# Nano_PCB.net
KiCad netlist of a schematic drawn in EAGLE
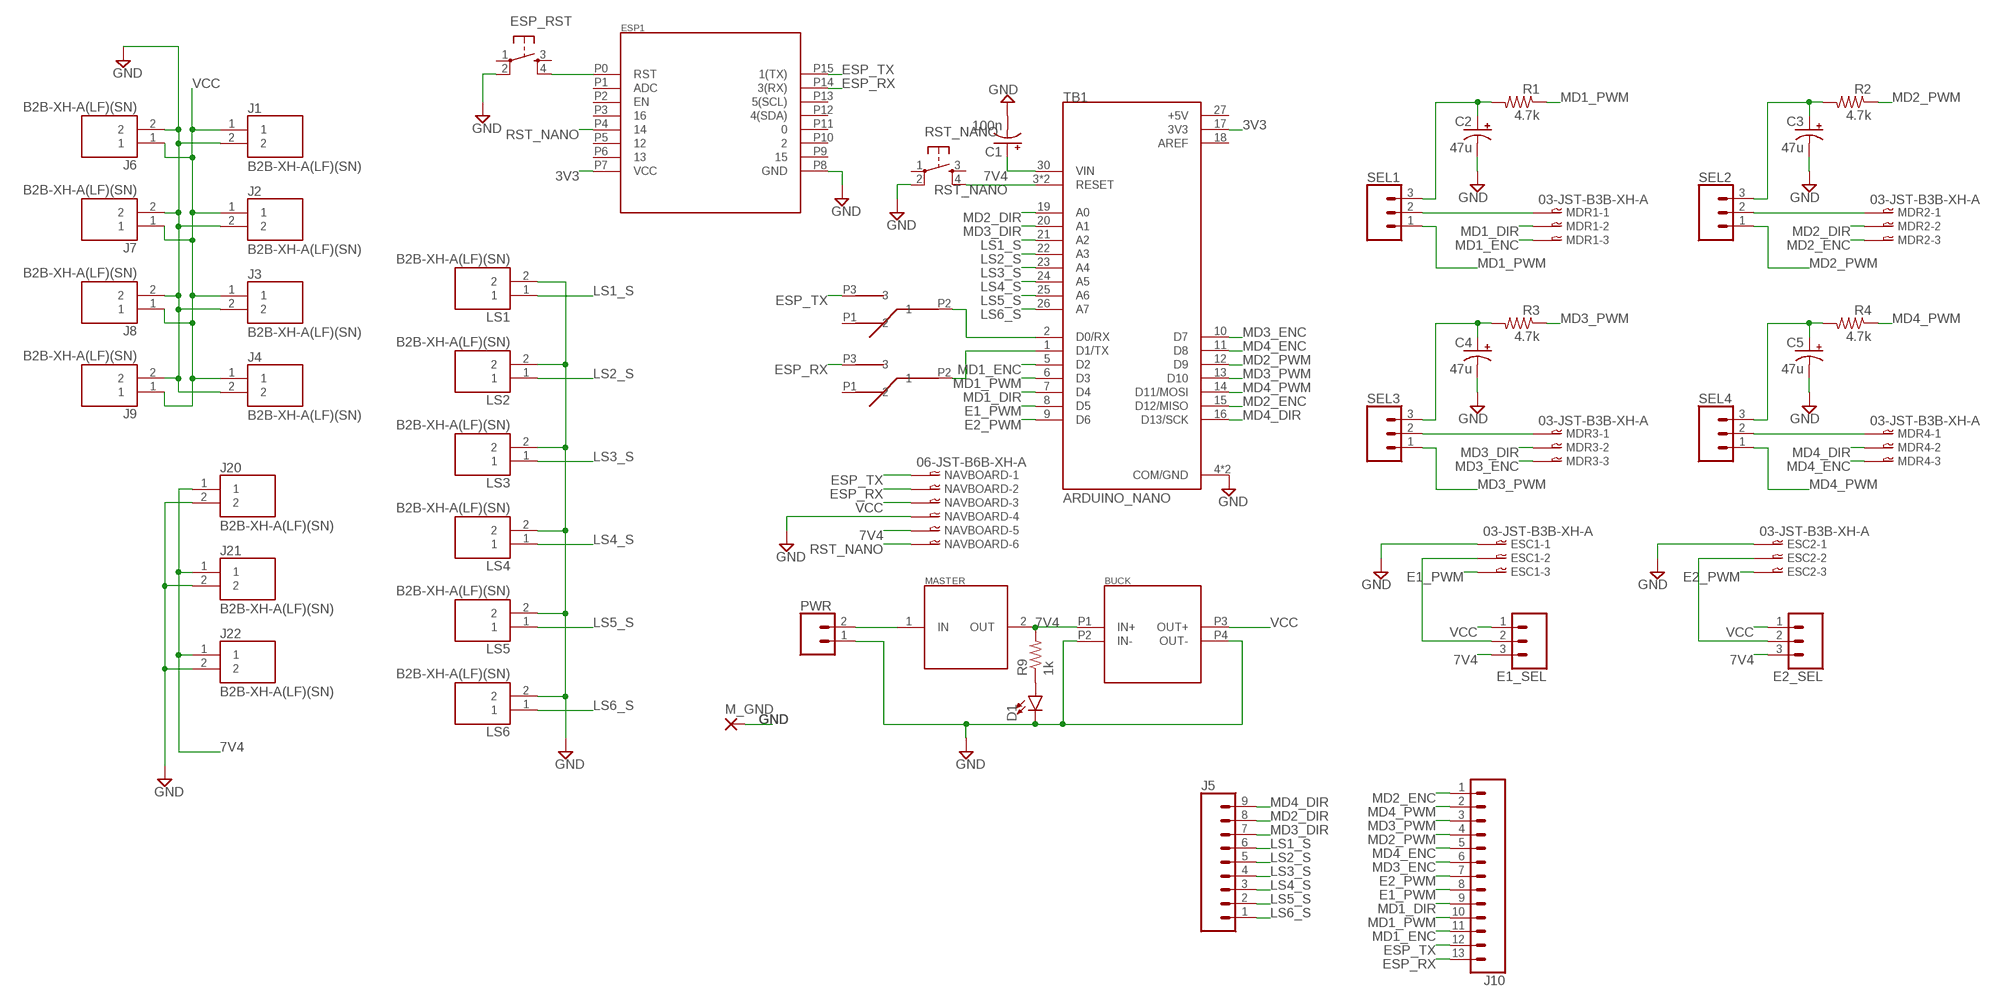
[diagram p0: schematic, sheet 1]

(export (version "E")
  (design (tool "Eeschema 10.0.6"))
  (components
    (comp (ref "BUCK")
      (value "5V_BUCK")
      (footprint "eagle-import:5V_BUCK")
      (libsource (lib "eagle-import") (part "5V_BUCK"))
    )
    (comp (ref "C1")
      (value "100n")
      (footprint "eagle-import:TT2D6")
      (libsource (lib "eagle-import") (part "CPOL-USTT2D6"))
    )
    (comp (ref "C2")
      (value "47u")
      (footprint "eagle-import:E2-5")
      (libsource (lib "eagle-import") (part "CPOL-USE2-5"))
    )
    (comp (ref "C3")
      (value "47u")
      (footprint "eagle-import:E2-5")
      (libsource (lib "eagle-import") (part "CPOL-USE2-5"))
    )
    (comp (ref "C4")
      (value "47u")
      (footprint "eagle-import:E2-5")
      (libsource (lib "eagle-import") (part "CPOL-USE2-5"))
    )
    (comp (ref "C5")
      (value "47u")
      (footprint "eagle-import:E2-5")
      (libsource (lib "eagle-import") (part "CPOL-USE2-5"))
    )
    (comp (ref "D1")
      (value "LED3MM")
      (footprint "eagle-import:LED_3MM")
      (libsource (lib "eagle-import") (part "LED3MM"))
    )
    (comp (ref "E1_SEL")
      (value "CONN_03")
      (footprint "eagle-import:1X03")
      (libsource (lib "eagle-import") (part "CONN_03"))
    )
    (comp (ref "E2_SEL")
      (value "CONN_03")
      (footprint "eagle-import:1X03")
      (libsource (lib "eagle-import") (part "CONN_03"))
    )
    (comp (ref "ESC1")
      (value "03-JST-B3B-XH-A")
      (footprint "eagle-import:B3B-XH")
      (libsource (lib "eagle-import") (part "03-JST-B3B-XH-A"))
    )
    (comp (ref "ESC2")
      (value "03-JST-B3B-XH-A")
      (footprint "eagle-import:B3B-XH")
      (libsource (lib "eagle-import") (part "03-JST-B3B-XH-A"))
    )
    (comp (ref "ESP1")
      (value "ESP07")
      (footprint "eagle-import:ESP07")
      (libsource (lib "eagle-import") (part "ESP07"))
    )
    (comp (ref "ESP_RST")
      (value "TAC_SWITCHPTH")
      (footprint "eagle-import:TACTILE-PTH")
      (libsource (lib "eagle-import") (part "TAC_SWITCHPTH"))
    )
    (comp (ref "J1")
      (value "B2B-XH-A(LF)(SN)")
      (footprint "eagle-import:JST_B2B-XH-A(LF)(SN)")
      (fields (field (name "MF") "JST Sales"))
      (libsource (lib "eagle-import") (part "B2B-XH-A(LF)(SN)"))
    )
    (comp (ref "J2")
      (value "B2B-XH-A(LF)(SN)")
      (footprint "eagle-import:JST_B2B-XH-A(LF)(SN)")
      (fields (field (name "MF") "JST Sales"))
      (libsource (lib "eagle-import") (part "B2B-XH-A(LF)(SN)"))
    )
    (comp (ref "J3")
      (value "B2B-XH-A(LF)(SN)")
      (footprint "eagle-import:JST_B2B-XH-A(LF)(SN)")
      (fields (field (name "MF") "JST Sales"))
      (libsource (lib "eagle-import") (part "B2B-XH-A(LF)(SN)"))
    )
    (comp (ref "J4")
      (value "B2B-XH-A(LF)(SN)")
      (footprint "eagle-import:JST_B2B-XH-A(LF)(SN)")
      (fields (field (name "MF") "JST Sales"))
      (libsource (lib "eagle-import") (part "B2B-XH-A(LF)(SN)"))
    )
    (comp (ref "J5")
      (value "CONN_09")
      (footprint "eagle-import:1X09")
      (libsource (lib "eagle-import") (part "CONN_09"))
    )
    (comp (ref "J6")
      (value "B2B-XH-A(LF)(SN)")
      (footprint "eagle-import:JST_B2B-XH-A(LF)(SN)")
      (fields (field (name "MF") "JST Sales"))
      (libsource (lib "eagle-import") (part "B2B-XH-A(LF)(SN)"))
    )
    (comp (ref "J7")
      (value "B2B-XH-A(LF)(SN)")
      (footprint "eagle-import:JST_B2B-XH-A(LF)(SN)")
      (fields (field (name "MF") "JST Sales"))
      (libsource (lib "eagle-import") (part "B2B-XH-A(LF)(SN)"))
    )
    (comp (ref "J8")
      (value "B2B-XH-A(LF)(SN)")
      (footprint "eagle-import:JST_B2B-XH-A(LF)(SN)")
      (fields (field (name "MF") "JST Sales"))
      (libsource (lib "eagle-import") (part "B2B-XH-A(LF)(SN)"))
    )
    (comp (ref "J9")
      (value "B2B-XH-A(LF)(SN)")
      (footprint "eagle-import:JST_B2B-XH-A(LF)(SN)")
      (fields (field (name "MF") "JST Sales"))
      (libsource (lib "eagle-import") (part "B2B-XH-A(LF)(SN)"))
    )
    (comp (ref "J10")
      (value "CONN_13")
      (footprint "eagle-import:1X13")
      (libsource (lib "eagle-import") (part "CONN_13"))
    )
    (comp (ref "J20")
      (value "B2B-XH-A(LF)(SN)")
      (footprint "eagle-import:JST_B2B-XH-A(LF)(SN)")
      (fields (field (name "MF") "JST Sales"))
      (libsource (lib "eagle-import") (part "B2B-XH-A(LF)(SN)"))
    )
    (comp (ref "J21")
      (value "B2B-XH-A(LF)(SN)")
      (footprint "eagle-import:JST_B2B-XH-A(LF)(SN)")
      (fields (field (name "MF") "JST Sales"))
      (libsource (lib "eagle-import") (part "B2B-XH-A(LF)(SN)"))
    )
    (comp (ref "J22")
      (value "B2B-XH-A(LF)(SN)")
      (footprint "eagle-import:JST_B2B-XH-A(LF)(SN)")
      (fields (field (name "MF") "JST Sales"))
      (libsource (lib "eagle-import") (part "B2B-XH-A(LF)(SN)"))
    )
    (comp (ref "LS1")
      (value "B2B-XH-A(LF)(SN)")
      (footprint "eagle-import:JST_B2B-XH-A(LF)(SN)")
      (fields (field (name "MF") "JST Sales"))
      (libsource (lib "eagle-import") (part "B2B-XH-A(LF)(SN)"))
    )
    (comp (ref "LS2")
      (value "B2B-XH-A(LF)(SN)")
      (footprint "eagle-import:JST_B2B-XH-A(LF)(SN)")
      (fields (field (name "MF") "JST Sales"))
      (libsource (lib "eagle-import") (part "B2B-XH-A(LF)(SN)"))
    )
    (comp (ref "LS3")
      (value "B2B-XH-A(LF)(SN)")
      (footprint "eagle-import:JST_B2B-XH-A(LF)(SN)")
      (fields (field (name "MF") "JST Sales"))
      (libsource (lib "eagle-import") (part "B2B-XH-A(LF)(SN)"))
    )
    (comp (ref "LS4")
      (value "B2B-XH-A(LF)(SN)")
      (footprint "eagle-import:JST_B2B-XH-A(LF)(SN)")
      (fields (field (name "MF") "JST Sales"))
      (libsource (lib "eagle-import") (part "B2B-XH-A(LF)(SN)"))
    )
    (comp (ref "LS5")
      (value "B2B-XH-A(LF)(SN)")
      (footprint "eagle-import:JST_B2B-XH-A(LF)(SN)")
      (fields (field (name "MF") "JST Sales"))
      (libsource (lib "eagle-import") (part "B2B-XH-A(LF)(SN)"))
    )
    (comp (ref "LS6")
      (value "B2B-XH-A(LF)(SN)")
      (footprint "eagle-import:JST_B2B-XH-A(LF)(SN)")
      (fields (field (name "MF") "JST Sales"))
      (libsource (lib "eagle-import") (part "B2B-XH-A(LF)(SN)"))
    )
    (comp (ref "MASTER")
      (value "MED_SWITCH")
      (footprint "eagle-import:MED_SWITCH")
      (libsource (lib "eagle-import") (part "MED_SWITCH"))
    )
    (comp (ref "MDR1")
      (value "03-JST-B3B-XH-A")
      (footprint "eagle-import:B3B-XH")
      (libsource (lib "eagle-import") (part "03-JST-B3B-XH-A"))
    )
    (comp (ref "MDR2")
      (value "03-JST-B3B-XH-A")
      (footprint "eagle-import:B3B-XH")
      (libsource (lib "eagle-import") (part "03-JST-B3B-XH-A"))
    )
    (comp (ref "MDR3")
      (value "03-JST-B3B-XH-A")
      (footprint "eagle-import:B3B-XH")
      (libsource (lib "eagle-import") (part "03-JST-B3B-XH-A"))
    )
    (comp (ref "MDR4")
      (value "03-JST-B3B-XH-A")
      (footprint "eagle-import:B3B-XH")
      (libsource (lib "eagle-import") (part "03-JST-B3B-XH-A"))
    )
    (comp (ref "M_GND")
      (value "WIREPADSMD5-2,5")
      (footprint "eagle-import:5-2,5")
      (libsource (lib "eagle-import") (part "WIREPADSMD5-2,5"))
    )
    (comp (ref "NAVBOARD")
      (value "06-JST-B6B-XH-A")
      (footprint "eagle-import:B6B-XH")
      (libsource (lib "eagle-import") (part "06-JST-B6B-XH-A"))
    )
    (comp (ref "PWR")
      (value "CONN_02PTH4")
      (footprint "eagle-import:1X02_XTRA_BIG")
      (libsource (lib "eagle-import") (part "CONN_02PTH4"))
    )
    (comp (ref "R1")
      (value "4.7k")
      (footprint "eagle-import:0204_7")
      (libsource (lib "eagle-import") (part "R-US_0204/7"))
    )
    (comp (ref "R2")
      (value "4.7k")
      (footprint "eagle-import:0204_7")
      (libsource (lib "eagle-import") (part "R-US_0204/7"))
    )
    (comp (ref "R3")
      (value "4.7k")
      (footprint "eagle-import:0204_7")
      (libsource (lib "eagle-import") (part "R-US_0204/7"))
    )
    (comp (ref "R4")
      (value "4.7k")
      (footprint "eagle-import:0204_7")
      (libsource (lib "eagle-import") (part "R-US_0204/7"))
    )
    (comp (ref "R9")
      (value "1k")
      (footprint "eagle-import:0204_7")
      (libsource (lib "eagle-import") (part "R-US_0204/7"))
    )
    (comp (ref "RST_NANO")
      (value "TAC_SWITCHPTH")
      (footprint "eagle-import:TACTILE-PTH")
      (libsource (lib "eagle-import") (part "TAC_SWITCHPTH"))
    )
    (comp (ref "SEL1")
      (value "CONN_03")
      (footprint "eagle-import:1X03")
      (libsource (lib "eagle-import") (part "CONN_03"))
    )
    (comp (ref "SEL2")
      (value "CONN_03")
      (footprint "eagle-import:1X03")
      (libsource (lib "eagle-import") (part "CONN_03"))
    )
    (comp (ref "SEL3")
      (value "CONN_03")
      (footprint "eagle-import:1X03")
      (libsource (lib "eagle-import") (part "CONN_03"))
    )
    (comp (ref "SEL4")
      (value "CONN_03")
      (footprint "eagle-import:1X03")
      (libsource (lib "eagle-import") (part "CONN_03"))
    )
    (comp (ref "TB1")
      (value "ARDUINO_NANO")
      (footprint "eagle-import:SHIELD_ARDUINO_NANO")
      (fields (field (name "MF") "Arduino") (field (name "MP") "Arduino Nano"))
      (libsource (lib "eagle-import") (part "ARDUINO_NANO"))
    )
    (comp (ref "U$1")
      (value "SLIDE_SWITCH")
      (footprint "eagle-import:SLIDE_SWITCH")
      (libsource (lib "eagle-import") (part "SLIDE_SWITCH"))
    )
    (comp (ref "U$2")
      (value "SLIDE_SWITCH")
      (footprint "eagle-import:SLIDE_SWITCH")
      (libsource (lib "eagle-import") (part "SLIDE_SWITCH"))
    )
  )
  (nets
    (net (code "1") (name "/+5V") (class "Default")
      (node (ref "TB1") (pin "27") (pinfunction "+5V_27") (pintype "power_in"))
    )
    (net (code "2") (name "/3V3") (class "Default")
      (node (ref "ESP1") (pin "P7") (pinfunction "VCC_P7") (pintype "bidirectional"))
      (node (ref "TB1") (pin "17") (pinfunction "3V3_17") (pintype "power_in"))
    )
    (net (code "3") (name "/7V4") (class "Default")
      (node (ref "BUCK") (pin "P1") (pinfunction "IN+_P1") (pintype "bidirectional"))
      (node (ref "C1") (pin "+") (pinfunction "+_+") (pintype "passive"))
      (node (ref "E1_SEL") (pin "3") (pinfunction "3_3") (pintype "passive"))
      (node (ref "E2_SEL") (pin "3") (pinfunction "3_3") (pintype "passive"))
      (node (ref "J20") (pin "1") (pinfunction "1_1") (pintype "passive"))
      (node (ref "J21") (pin "1") (pinfunction "1_1") (pintype "passive"))
      (node (ref "J22") (pin "1") (pinfunction "1_1") (pintype "passive"))
      (node (ref "MASTER") (pin "2") (pinfunction "OUT_2") (pintype "bidirectional"))
      (node (ref "NAVBOARD") (pin "P$5") (pinfunction "1_P$5") (pintype "passive"))
      (node (ref "R9") (pin "2") (pinfunction "2_2") (pintype "passive"))
      (node (ref "TB1") (pin "30") (pinfunction "VIN_30") (pintype "input"))
    )
    (net (code "4") (name "/AREF") (class "Default")
      (node (ref "TB1") (pin "18") (pinfunction "AREF_18") (pintype "power_in"))
    )
    (net (code "5") (name "/E1_PWM") (class "Default")
      (node (ref "ESC1") (pin "P$3") (pinfunction "1_P$3") (pintype "passive"))
      (node (ref "J10") (pin "8") (pinfunction "8_8") (pintype "passive"))
      (node (ref "TB1") (pin "8") (pinfunction "D5_8") (pintype "bidirectional"))
    )
    (net (code "6") (name "/E2_PWM") (class "Default")
      (node (ref "ESC2") (pin "P$3") (pinfunction "1_P$3") (pintype "passive"))
      (node (ref "J10") (pin "7") (pinfunction "7_7") (pintype "passive"))
      (node (ref "TB1") (pin "9") (pinfunction "D6_9") (pintype "bidirectional"))
    )
    (net (code "7") (name "/ESP_RX") (class "Default")
      (node (ref "ESP1") (pin "P14") (pinfunction "3(RX)_P14") (pintype "bidirectional"))
      (node (ref "J10") (pin "13") (pinfunction "13_13") (pintype "passive"))
      (node (ref "NAVBOARD") (pin "P$2") (pinfunction "1_P$2") (pintype "passive"))
      (node (ref "U$2") (pin "P3") (pinfunction "3_P3") (pintype "bidirectional"))
    )
    (net (code "8") (name "/ESP_TX") (class "Default")
      (node (ref "ESP1") (pin "P15") (pinfunction "1(TX)_P15") (pintype "bidirectional"))
      (node (ref "J10") (pin "12") (pinfunction "12_12") (pintype "passive"))
      (node (ref "NAVBOARD") (pin "P$1") (pinfunction "1_P$1") (pintype "passive"))
      (node (ref "U$1") (pin "P3") (pinfunction "3_P3") (pintype "bidirectional"))
    )
    (net (code "9") (name "/LS1_S") (class "Default")
      (node (ref "J5") (pin "6") (pinfunction "6_6") (pintype "passive"))
      (node (ref "LS1") (pin "1") (pinfunction "1_1") (pintype "passive"))
      (node (ref "TB1") (pin "21") (pinfunction "A2_21") (pintype "input"))
    )
    (net (code "10") (name "/LS2_S") (class "Default")
      (node (ref "J5") (pin "5") (pinfunction "5_5") (pintype "passive"))
      (node (ref "LS2") (pin "1") (pinfunction "1_1") (pintype "passive"))
      (node (ref "TB1") (pin "22") (pinfunction "A3_22") (pintype "input"))
    )
    (net (code "11") (name "/LS3_S") (class "Default")
      (node (ref "J5") (pin "4") (pinfunction "4_4") (pintype "passive"))
      (node (ref "LS3") (pin "1") (pinfunction "1_1") (pintype "passive"))
      (node (ref "TB1") (pin "23") (pinfunction "A4_23") (pintype "input"))
    )
    (net (code "12") (name "/LS4_S") (class "Default")
      (node (ref "J5") (pin "3") (pinfunction "3_3") (pintype "passive"))
      (node (ref "LS4") (pin "1") (pinfunction "1_1") (pintype "passive"))
      (node (ref "TB1") (pin "24") (pinfunction "A5_24") (pintype "input"))
    )
    (net (code "13") (name "/LS5_S") (class "Default")
      (node (ref "J5") (pin "2") (pinfunction "2_2") (pintype "passive"))
      (node (ref "LS5") (pin "1") (pinfunction "1_1") (pintype "passive"))
      (node (ref "TB1") (pin "25") (pinfunction "A6_25") (pintype "input"))
    )
    (net (code "14") (name "/LS6_S") (class "Default")
      (node (ref "J5") (pin "1") (pinfunction "1_1") (pintype "passive"))
      (node (ref "LS6") (pin "1") (pinfunction "1_1") (pintype "passive"))
      (node (ref "TB1") (pin "26") (pinfunction "A7_26") (pintype "input"))
    )
    (net (code "15") (name "/MD1_DIR") (class "Default")
      (node (ref "J10") (pin "9") (pinfunction "9_9") (pintype "passive"))
      (node (ref "MDR1") (pin "P$2") (pinfunction "1_P$2") (pintype "passive"))
      (node (ref "TB1") (pin "7") (pinfunction "D4_7") (pintype "bidirectional"))
    )
    (net (code "16") (name "/MD1_ENC") (class "Default")
      (node (ref "J10") (pin "11") (pinfunction "11_11") (pintype "passive"))
      (node (ref "MDR1") (pin "P$3") (pinfunction "1_P$3") (pintype "passive"))
      (node (ref "TB1") (pin "5") (pinfunction "D2_5") (pintype "bidirectional"))
    )
    (net (code "17") (name "/MD1_PWM") (class "Default")
      (node (ref "J10") (pin "10") (pinfunction "10_10") (pintype "passive"))
      (node (ref "R1") (pin "1") (pinfunction "1_1") (pintype "passive"))
      (node (ref "SEL1") (pin "1") (pinfunction "1_1") (pintype "passive"))
      (node (ref "TB1") (pin "6") (pinfunction "D3_6") (pintype "bidirectional"))
    )
    (net (code "18") (name "/MD2_DIR") (class "Default")
      (node (ref "J5") (pin "8") (pinfunction "8_8") (pintype "passive"))
      (node (ref "MDR2") (pin "P$2") (pinfunction "1_P$2") (pintype "passive"))
      (node (ref "TB1") (pin "19") (pinfunction "A0_19") (pintype "input"))
    )
    (net (code "19") (name "/MD2_ENC") (class "Default")
      (node (ref "J10") (pin "1") (pinfunction "1_1") (pintype "passive"))
      (node (ref "MDR2") (pin "P$3") (pinfunction "1_P$3") (pintype "passive"))
      (node (ref "TB1") (pin "15") (pinfunction "D12/MISO_15") (pintype "bidirectional"))
    )
    (net (code "20") (name "/MD2_PWM") (class "Default")
      (node (ref "J10") (pin "4") (pinfunction "4_4") (pintype "passive"))
      (node (ref "R2") (pin "1") (pinfunction "1_1") (pintype "passive"))
      (node (ref "SEL2") (pin "1") (pinfunction "1_1") (pintype "passive"))
      (node (ref "TB1") (pin "12") (pinfunction "D9_12") (pintype "bidirectional"))
    )
    (net (code "21") (name "/MD3_DIR") (class "Default")
      (node (ref "J5") (pin "7") (pinfunction "7_7") (pintype "passive"))
      (node (ref "MDR3") (pin "P$2") (pinfunction "1_P$2") (pintype "passive"))
      (node (ref "TB1") (pin "20") (pinfunction "A1_20") (pintype "input"))
    )
    (net (code "22") (name "/MD3_ENC") (class "Default")
      (node (ref "J10") (pin "6") (pinfunction "6_6") (pintype "passive"))
      (node (ref "MDR3") (pin "P$3") (pinfunction "1_P$3") (pintype "passive"))
      (node (ref "TB1") (pin "10") (pinfunction "D7_10") (pintype "bidirectional"))
    )
    (net (code "23") (name "/MD3_PWM") (class "Default")
      (node (ref "J10") (pin "3") (pinfunction "3_3") (pintype "passive"))
      (node (ref "R3") (pin "1") (pinfunction "1_1") (pintype "passive"))
      (node (ref "SEL3") (pin "1") (pinfunction "1_1") (pintype "passive"))
      (node (ref "TB1") (pin "13") (pinfunction "D10_13") (pintype "bidirectional"))
    )
    (net (code "24") (name "/MD4_DIR") (class "Default")
      (node (ref "J5") (pin "9") (pinfunction "9_9") (pintype "passive"))
      (node (ref "MDR4") (pin "P$2") (pinfunction "1_P$2") (pintype "passive"))
      (node (ref "TB1") (pin "16") (pinfunction "D13/SCK_16") (pintype "bidirectional"))
    )
    (net (code "25") (name "/MD4_ENC") (class "Default")
      (node (ref "J10") (pin "5") (pinfunction "5_5") (pintype "passive"))
      (node (ref "MDR4") (pin "P$3") (pinfunction "1_P$3") (pintype "passive"))
      (node (ref "TB1") (pin "11") (pinfunction "D8_11") (pintype "bidirectional"))
    )
    (net (code "26") (name "/MD4_PWM") (class "Default")
      (node (ref "J10") (pin "2") (pinfunction "2_2") (pintype "passive"))
      (node (ref "R4") (pin "1") (pinfunction "1_1") (pintype "passive"))
      (node (ref "SEL4") (pin "1") (pinfunction "1_1") (pintype "passive"))
      (node (ref "TB1") (pin "14") (pinfunction "D11/MOSI_14") (pintype "bidirectional"))
    )
    (net (code "27") (name "/RST_NANO") (class "Default")
      (node (ref "ESP1") (pin "P4") (pinfunction "14_P4") (pintype "bidirectional"))
      (node (ref "NAVBOARD") (pin "P$6") (pinfunction "1_P$6") (pintype "passive"))
      (node (ref "RST_NANO") (pin "4") (pinfunction "4_4") (pintype "passive"))
      (node (ref "TB1") (pin "28") (pinfunction "RESET_28") (pintype "input"))
      (node (ref "TB1") (pin "3") (pinfunction "RESET_3") (pintype "input"))
    )
    (net (code "28") (name "/VCC") (class "Default")
      (node (ref "BUCK") (pin "P3") (pinfunction "OUT+_P3") (pintype "bidirectional"))
      (node (ref "E1_SEL") (pin "1") (pinfunction "1_1") (pintype "passive"))
      (node (ref "E2_SEL") (pin "1") (pinfunction "1_1") (pintype "passive"))
      (node (ref "J1") (pin "1") (pinfunction "1_1") (pintype "passive"))
      (node (ref "J2") (pin "1") (pinfunction "1_1") (pintype "passive"))
      (node (ref "J3") (pin "1") (pinfunction "1_1") (pintype "passive"))
      (node (ref "J4") (pin "1") (pinfunction "1_1") (pintype "passive"))
      (node (ref "J6") (pin "1") (pinfunction "1_1") (pintype "passive"))
      (node (ref "J7") (pin "1") (pinfunction "1_1") (pintype "passive"))
      (node (ref "J8") (pin "1") (pinfunction "1_1") (pintype "passive"))
      (node (ref "J9") (pin "1") (pinfunction "1_1") (pintype "passive"))
      (node (ref "NAVBOARD") (pin "P$3") (pinfunction "1_P$3") (pintype "passive"))
    )
    (net (code "29") (name "GND") (class "Default")
      (node (ref "BUCK") (pin "P2") (pinfunction "IN-_P2") (pintype "bidirectional"))
      (node (ref "BUCK") (pin "P4") (pinfunction "OUT-_P4") (pintype "bidirectional"))
      (node (ref "C1") (pin "-") (pinfunction "-_-") (pintype "passive"))
      (node (ref "C2") (pin "-") (pinfunction "-_-") (pintype "passive"))
      (node (ref "C3") (pin "-") (pinfunction "-_-") (pintype "passive"))
      (node (ref "C4") (pin "-") (pinfunction "-_-") (pintype "passive"))
      (node (ref "C5") (pin "-") (pinfunction "-_-") (pintype "passive"))
      (node (ref "D1") (pin "K") (pinfunction "C_K") (pintype "passive"))
      (node (ref "ESC1") (pin "P$1") (pinfunction "1_P$1") (pintype "passive"))
      (node (ref "ESC2") (pin "P$1") (pinfunction "1_P$1") (pintype "passive"))
      (node (ref "ESP1") (pin "P8") (pinfunction "GND_P8") (pintype "bidirectional"))
      (node (ref "ESP_RST") (pin "2") (pinfunction "2_2") (pintype "passive"))
      (node (ref "J1") (pin "2") (pinfunction "2_2") (pintype "passive"))
      (node (ref "J2") (pin "2") (pinfunction "2_2") (pintype "passive"))
      (node (ref "J20") (pin "2") (pinfunction "2_2") (pintype "passive"))
      (node (ref "J21") (pin "2") (pinfunction "2_2") (pintype "passive"))
      (node (ref "J22") (pin "2") (pinfunction "2_2") (pintype "passive"))
      (node (ref "J3") (pin "2") (pinfunction "2_2") (pintype "passive"))
      (node (ref "J4") (pin "2") (pinfunction "2_2") (pintype "passive"))
      (node (ref "J6") (pin "2") (pinfunction "2_2") (pintype "passive"))
      (node (ref "J7") (pin "2") (pinfunction "2_2") (pintype "passive"))
      (node (ref "J8") (pin "2") (pinfunction "2_2") (pintype "passive"))
      (node (ref "J9") (pin "2") (pinfunction "2_2") (pintype "passive"))
      (node (ref "LS1") (pin "2") (pinfunction "2_2") (pintype "passive"))
      (node (ref "LS2") (pin "2") (pinfunction "2_2") (pintype "passive"))
      (node (ref "LS3") (pin "2") (pinfunction "2_2") (pintype "passive"))
      (node (ref "LS4") (pin "2") (pinfunction "2_2") (pintype "passive"))
      (node (ref "LS5") (pin "2") (pinfunction "2_2") (pintype "passive"))
      (node (ref "LS6") (pin "2") (pinfunction "2_2") (pintype "passive"))
      (node (ref "M_GND") (pin "1") (pinfunction "P_1") (pintype "passive"))
      (node (ref "NAVBOARD") (pin "P$4") (pinfunction "1_P$4") (pintype "passive"))
      (node (ref "PWR") (pin "1") (pinfunction "1_1") (pintype "passive"))
      (node (ref "RST_NANO") (pin "2") (pinfunction "2_2") (pintype "passive"))
      (node (ref "TB1") (pin "29") (pinfunction "COM/GND_29") (pintype "power_in"))
      (node (ref "TB1") (pin "4") (pinfunction "COM/GND_4") (pintype "power_in"))
    )
    (net (code "30") (name "Net-(C2-Pad+)") (class "Default")
      (node (ref "C2") (pin "+") (pinfunction "+_+") (pintype "passive"))
      (node (ref "R1") (pin "2") (pinfunction "2_2") (pintype "passive"))
      (node (ref "SEL1") (pin "3") (pinfunction "3_3") (pintype "passive"))
    )
    (net (code "31") (name "Net-(C3-Pad+)") (class "Default")
      (node (ref "C3") (pin "+") (pinfunction "+_+") (pintype "passive"))
      (node (ref "R2") (pin "2") (pinfunction "2_2") (pintype "passive"))
      (node (ref "SEL2") (pin "3") (pinfunction "3_3") (pintype "passive"))
    )
    (net (code "32") (name "Net-(C4-Pad+)") (class "Default")
      (node (ref "C4") (pin "+") (pinfunction "+_+") (pintype "passive"))
      (node (ref "R3") (pin "2") (pinfunction "2_2") (pintype "passive"))
      (node (ref "SEL3") (pin "3") (pinfunction "3_3") (pintype "passive"))
    )
    (net (code "33") (name "Net-(C5-Pad+)") (class "Default")
      (node (ref "C5") (pin "+") (pinfunction "+_+") (pintype "passive"))
      (node (ref "R4") (pin "2") (pinfunction "2_2") (pintype "passive"))
      (node (ref "SEL4") (pin "3") (pinfunction "3_3") (pintype "passive"))
    )
    (net (code "34") (name "Net-(D1-PadA)") (class "Default")
      (node (ref "D1") (pin "A") (pinfunction "A_A") (pintype "passive"))
      (node (ref "R9") (pin "1") (pinfunction "1_1") (pintype "passive"))
    )
    (net (code "35") (name "Net-(ESC1B-1)") (class "Default")
      (node (ref "E1_SEL") (pin "2") (pinfunction "2_2") (pintype "passive"))
      (node (ref "ESC1") (pin "P$2") (pinfunction "1_P$2") (pintype "passive"))
    )
    (net (code "36") (name "Net-(ESC2B-1)") (class "Default")
      (node (ref "E2_SEL") (pin "2") (pinfunction "2_2") (pintype "passive"))
      (node (ref "ESC2") (pin "P$2") (pinfunction "1_P$2") (pintype "passive"))
    )
    (net (code "37") (name "Net-(ESP1-RST)") (class "Default")
      (node (ref "ESP1") (pin "P0") (pinfunction "RST_P0") (pintype "bidirectional"))
      (node (ref "ESP_RST") (pin "4") (pinfunction "4_4") (pintype "passive"))
    )
    (net (code "38") (name "Net-(MASTER-IN)") (class "Default")
      (node (ref "MASTER") (pin "1") (pinfunction "IN_1") (pintype "bidirectional"))
      (node (ref "PWR") (pin "2") (pinfunction "2_2") (pintype "passive"))
    )
    (net (code "39") (name "Net-(MDR1A-1)") (class "Default")
      (node (ref "MDR1") (pin "P$1") (pinfunction "1_P$1") (pintype "passive"))
      (node (ref "SEL1") (pin "2") (pinfunction "2_2") (pintype "passive"))
    )
    (net (code "40") (name "Net-(MDR2A-1)") (class "Default")
      (node (ref "MDR2") (pin "P$1") (pinfunction "1_P$1") (pintype "passive"))
      (node (ref "SEL2") (pin "2") (pinfunction "2_2") (pintype "passive"))
    )
    (net (code "41") (name "Net-(MDR3A-1)") (class "Default")
      (node (ref "MDR3") (pin "P$1") (pinfunction "1_P$1") (pintype "passive"))
      (node (ref "SEL3") (pin "2") (pinfunction "2_2") (pintype "passive"))
    )
    (net (code "42") (name "Net-(MDR4A-1)") (class "Default")
      (node (ref "MDR4") (pin "P$1") (pinfunction "1_P$1") (pintype "passive"))
      (node (ref "SEL4") (pin "2") (pinfunction "2_2") (pintype "passive"))
    )
    (net (code "43") (name "Net-(TB1-D0{slash}RX)") (class "Default")
      (node (ref "TB1") (pin "2") (pinfunction "D0/RX_2") (pintype "bidirectional"))
      (node (ref "U$1") (pin "P2") (pinfunction "1_P2") (pintype "bidirectional"))
    )
    (net (code "44") (name "Net-(TB1-D1{slash}TX)") (class "Default")
      (node (ref "TB1") (pin "1") (pinfunction "D1/TX_1") (pintype "bidirectional"))
      (node (ref "U$2") (pin "P2") (pinfunction "1_P2") (pintype "bidirectional"))
    )
    (net (code "45") (name "unconnected-(ESP1-0-PadP11)") (class "Default")
      (node (ref "ESP1") (pin "P11") (pinfunction "0_P11") (pintype "bidirectional"))
    )
    (net (code "46") (name "unconnected-(ESP1-2-PadP10)") (class "Default")
      (node (ref "ESP1") (pin "P10") (pinfunction "2_P10") (pintype "bidirectional"))
    )
    (net (code "47") (name "unconnected-(ESP1-4(SDA)-PadP12)") (class "Default")
      (node (ref "ESP1") (pin "P12") (pinfunction "4(SDA)_P12") (pintype "bidirectional"))
    )
    (net (code "48") (name "unconnected-(ESP1-5(SCL)-PadP13)") (class "Default")
      (node (ref "ESP1") (pin "P13") (pinfunction "5(SCL)_P13") (pintype "bidirectional"))
    )
    (net (code "49") (name "unconnected-(ESP1-12-PadP5)") (class "Default")
      (node (ref "ESP1") (pin "P5") (pinfunction "12_P5") (pintype "bidirectional"))
    )
    (net (code "50") (name "unconnected-(ESP1-13-PadP6)") (class "Default")
      (node (ref "ESP1") (pin "P6") (pinfunction "13_P6") (pintype "bidirectional"))
    )
    (net (code "51") (name "unconnected-(ESP1-15-PadP9)") (class "Default")
      (node (ref "ESP1") (pin "P9") (pinfunction "15_P9") (pintype "bidirectional"))
    )
    (net (code "52") (name "unconnected-(ESP1-16-PadP3)") (class "Default")
      (node (ref "ESP1") (pin "P3") (pinfunction "16_P3") (pintype "bidirectional"))
    )
    (net (code "53") (name "unconnected-(ESP1-ADC-PadP1)") (class "Default")
      (node (ref "ESP1") (pin "P1") (pinfunction "ADC_P1") (pintype "bidirectional"))
    )
    (net (code "54") (name "unconnected-(ESP1-EN-PadP2)") (class "Default")
      (node (ref "ESP1") (pin "P2") (pinfunction "EN_P2") (pintype "bidirectional"))
    )
    (net (code "55") (name "unconnected-(ESP_RST-Pad1)") (class "Default")
      (node (ref "ESP_RST") (pin "1") (pinfunction "1_1") (pintype "passive"))
    )
    (net (code "56") (name "unconnected-(ESP_RST-Pad3)") (class "Default")
      (node (ref "ESP_RST") (pin "3") (pinfunction "3_3") (pintype "passive"))
    )
    (net (code "57") (name "unconnected-(RST_NANO-Pad1)") (class "Default")
      (node (ref "RST_NANO") (pin "1") (pinfunction "1_1") (pintype "passive"))
    )
    (net (code "58") (name "unconnected-(RST_NANO-Pad3)") (class "Default")
      (node (ref "RST_NANO") (pin "3") (pinfunction "3_3") (pintype "passive"))
    )
    (net (code "59") (name "unconnected-(U$1-2-PadP1)") (class "Default")
      (node (ref "U$1") (pin "P1") (pinfunction "2_P1") (pintype "bidirectional"))
    )
    (net (code "60") (name "unconnected-(U$2-2-PadP1)") (class "Default")
      (node (ref "U$2") (pin "P1") (pinfunction "2_P1") (pintype "bidirectional"))
    )
  )
)
